# CC_pwr-moteur.net
KiCad netlist of a schematic drawn in Altium Designer
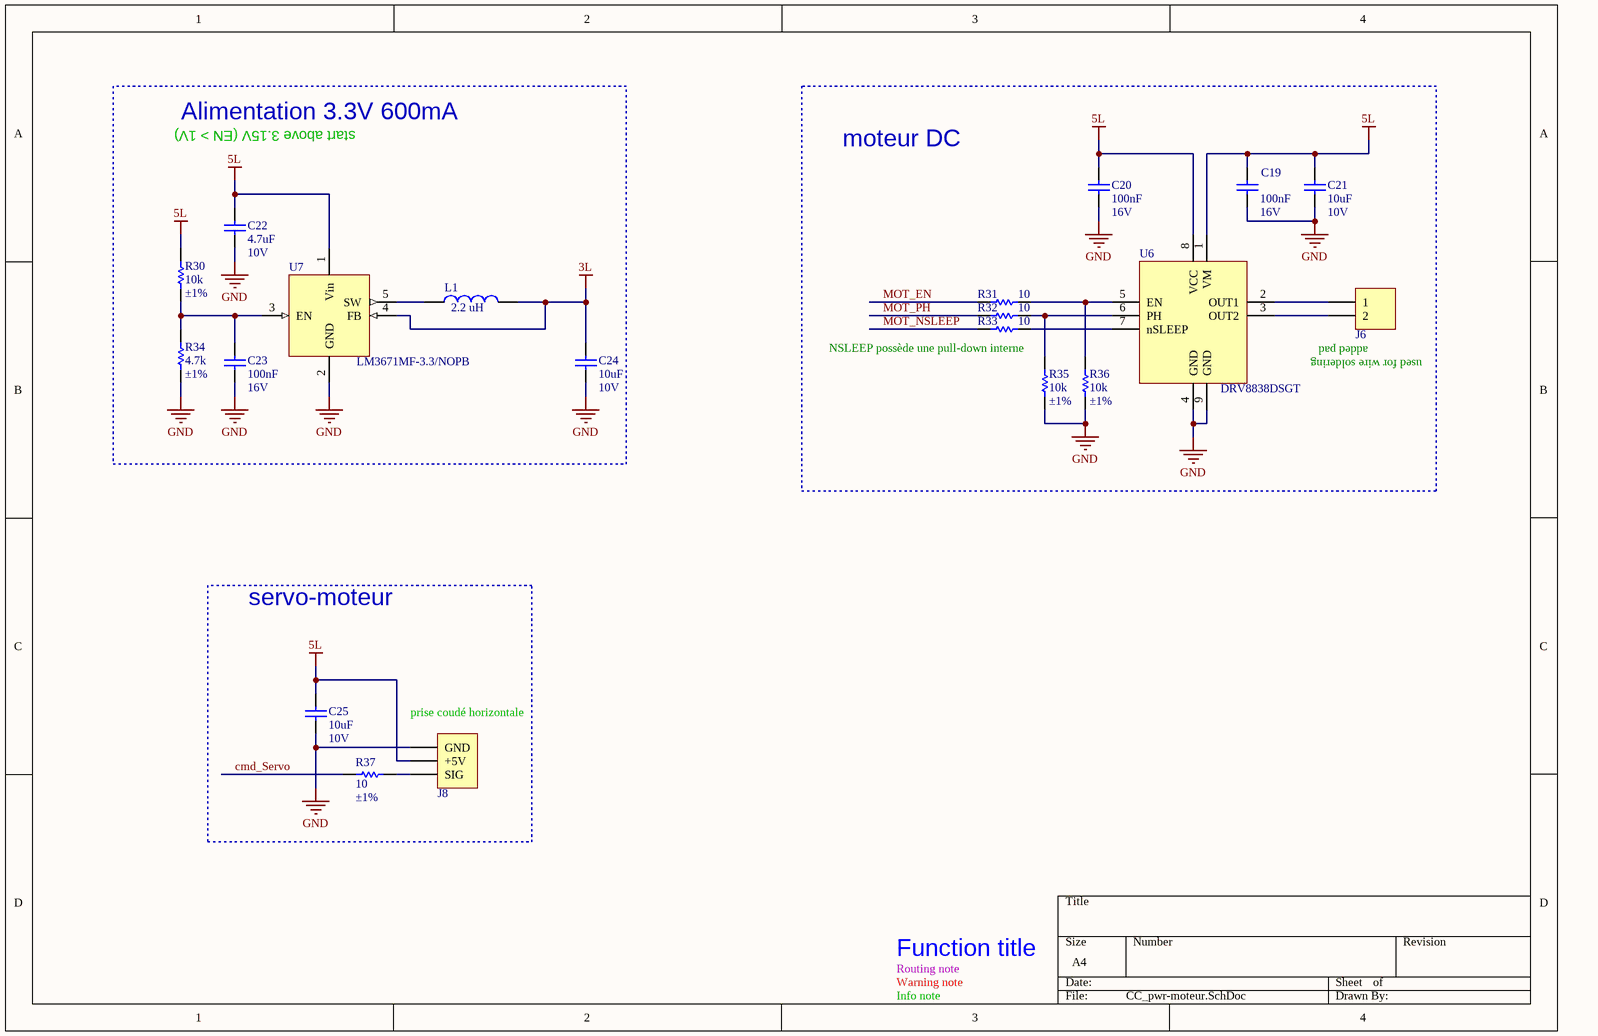
[diagram p0: CC_pwr-moteur.SchDoc]

(export (version "E")
  (design (tool "Eeschema 10.0.6"))
  (components
    (comp (ref "C19")
      (value "100nF")
      (footprint "WCAP-CSGP_0402, 1x0.5x0.5")
      (description "CAP CER 100nF 16V X7R 0402")
      (fields
        (field (name "MANUFACTURER") "Wurth Elektronik")
        (field (name "MANUFACTURER PART NUMBER") "885012205037")
        (field (name "RATEDVOLTAGE") "16V")
      )
      (libsource (lib "Condensateur") (part "WCAP-CSGP, 885012205037"))
    )
    (comp (ref "C20")
      (value "100nF")
      (footprint "WCAP-CSGP_0402, 1x0.5x0.5")
      (description "CAP CER 100nF 16V X7R 0402")
      (fields
        (field (name "MANUFACTURER") "Wurth Elektronik")
        (field (name "MANUFACTURER PART NUMBER") "885012205037")
        (field (name "RATEDVOLTAGE") "16V")
      )
      (libsource (lib "Condensateur") (part "WCAP-CSGP, 885012205037"))
    )
    (comp (ref "C21")
      (value "10uF")
      (footprint "WCAP-CSGP_0805, 2x1.25x1.25")
      (description "CAP CER 10uF 10V X7R 0805")
      (fields
        (field (name "MANUFACTURER") "Wurth Elektronik")
        (field (name "MANUFACTURER PART NUMBER") "885012207026")
        (field (name "RATEDVOLTAGE") "10V")
      )
      (libsource (lib "Condensateur") (part "WCAP-CSGP, 885012207026"))
    )
    (comp (ref "C22")
      (value "4.7uF")
      (footprint "WCAP-CSGP_0603, 1.6x0.8x0.8")
      (description "CAP CER 4.7UF 10V X5R 0603")
      (fields
        (field (name "MANUFACTURER") "Wurth Elektronik")
        (field (name "MANUFACTURER PART NUMBER") "885012106012")
        (field (name "RATEDVOLTAGE") "10V")
      )
      (libsource (lib "Condensateur") (part "WCAP-CSGP, 885012106012"))
    )
    (comp (ref "C23")
      (value "100nF")
      (footprint "WCAP-CSGP_0402, 1x0.5x0.5")
      (description "CAP CER 100nF 16V X7R 0402")
      (fields
        (field (name "MANUFACTURER") "Wurth Elektronik")
        (field (name "MANUFACTURER PART NUMBER") "885012205037")
        (field (name "RATEDVOLTAGE") "16V")
      )
      (libsource (lib "Condensateur") (part "WCAP-CSGP, 885012205037"))
    )
    (comp (ref "C24")
      (value "10uF")
      (footprint "WCAP-CSGP_0805, 2x1.25x1.25")
      (description "CAP CER 10uF 10V X7R 0805")
      (fields
        (field (name "MANUFACTURER") "Wurth Elektronik")
        (field (name "MANUFACTURER PART NUMBER") "885012207026")
        (field (name "RATEDVOLTAGE") "10V")
      )
      (libsource (lib "Condensateur") (part "WCAP-CSGP, 885012207026"))
    )
    (comp (ref "C25")
      (value "10uF")
      (footprint "WCAP-CSGP_0805, 2x1.25x1.25")
      (description "CAP CER 10uF 10V X7R 0805")
      (fields
        (field (name "MANUFACTURER") "Wurth Elektronik")
        (field (name "MANUFACTURER PART NUMBER") "885012207026")
        (field (name "RATEDVOLTAGE") "10V")
      )
      (libsource (lib "Condensateur") (part "WCAP-CSGP, 885012207026"))
    )
    (comp (ref "J6")
      (value "653102131822")
      (footprint "653102131822")
      (description "WR-WTB 2 horiz. 1.25mm")
      (fields (field (name "MANUFACTURER") "Wurth Electronics Inc."))
      (libsource (lib "Connecteurs") (part "653102131822"))
    )
    (comp (ref "J8")
      (value "61300311021")
      (footprint "61300311021")
      (description "CONN HEADER 3p horiz. 2.54mm")
      (fields (field (name "MANUFACTURER") "Wurth Electronics Inc."))
      (libsource (lib "Connecteurs") (part "61300311021"))
    )
    (comp (ref "L1")
      (value "2.2 uH")
      (footprint "WE-LQS_2010")
      (description "FIXED IND 2.2UH 960MA 220 MOHM")
      (fields
        (field (name "MANUFACTURER") "Wurth Elektronik")
        (field (name "MANUFACTURER PART NUMBER") "74404020022")
      )
      (libsource (lib "Inductance") (part "74404020022"))
    )
    (comp (ref "R30")
      (value "10k")
      (footprint "RESC1005X04N")
      (description "RES SMD 10K OHM 1% 1/16W 0402")
      (fields
        (field (name "POWER") "63mW")
        (field (name "MANUFACTURER") "Yageo")
        (field (name "PRECISION") "±1%")
      )
      (libsource (lib "Resistance") (part "RC0402FR-0710KL"))
    )
    (comp (ref "R31")
      (value "10")
      (footprint "RESC1005X04N")
      (description "RES SMD 10 OHM 1% 1/16W 0402")
      (fields (field (name "POWER") "63mW") (field (name "MANUFACTURER") "Yageo"))
      (libsource (lib "Resistance") (part "RC0402FR-0710RL"))
    )
    (comp (ref "R32")
      (value "10")
      (footprint "RESC1005X04N")
      (description "RES SMD 10 OHM 1% 1/16W 0402")
      (fields (field (name "POWER") "63mW") (field (name "MANUFACTURER") "Yageo"))
      (libsource (lib "Resistance") (part "RC0402FR-0710RL"))
    )
    (comp (ref "R33")
      (value "10")
      (footprint "RESC1005X04N")
      (description "RES SMD 10 OHM 1% 1/16W 0402")
      (fields (field (name "POWER") "63mW") (field (name "MANUFACTURER") "Yageo"))
      (libsource (lib "Resistance") (part "RC0402FR-0710RL"))
    )
    (comp (ref "R34")
      (value "4.7k")
      (footprint "RESC1005X04N")
      (description "RES SMD 4K7 OHM 1% 1/16W 0402")
      (fields
        (field (name "POWER") "63mW")
        (field (name "MANUFACTURER") "Yageo")
        (field (name "PRECISION") "±1%")
      )
      (libsource (lib "Resistance") (part "RC0402FR-074K7L"))
    )
    (comp (ref "R35")
      (value "10k")
      (footprint "RESC1005X04N")
      (description "RES SMD 10K OHM 1% 1/16W 0402")
      (fields
        (field (name "POWER") "63mW")
        (field (name "MANUFACTURER") "Yageo")
        (field (name "PRECISION") "±1%")
      )
      (libsource (lib "Resistance") (part "RC0402FR-0710KL"))
    )
    (comp (ref "R36")
      (value "10k")
      (footprint "RESC1005X04N")
      (description "RES SMD 10K OHM 1% 1/16W 0402")
      (fields
        (field (name "POWER") "63mW")
        (field (name "MANUFACTURER") "Yageo")
        (field (name "PRECISION") "±1%")
      )
      (libsource (lib "Resistance") (part "RC0402FR-0710KL"))
    )
    (comp (ref "R37")
      (value "10")
      (footprint "RESC1005X04N")
      (description "RES SMD 10 OHM 1% 1/16W 0402")
      (fields
        (field (name "POWER") "63mW")
        (field (name "MANUFACTURER") "Yageo")
        (field (name "PRECISION") "±1%")
      )
      (libsource (lib "Resistance") (part "RC0402FR-0710RL"))
    )
    (comp (ref "U6")
      (value "DRV8838DSGT")
      (footprint "PSON50P200X80_HS-9N")
      (description "IC BRIDGE DRIVER PAR 8WSON")
      (fields (field (name "MANUFACTURER") "Texas Instruments"))
      (libsource (lib "CI") (part "DRV8838DSGT"))
    )
    (comp (ref "U7")
      (value "LM3671MF-3.3/NOPB")
      (footprint "SOT23-5")
      (description "IC REG BUCK 3.3V 0.6A SYNC SOT23")
      (fields (field (name "MANUFACTURER") "Texas Instruments"))
      (libsource (lib "Alimentation") (part "LM3671MF-3.3/NOPB"))
    )
  )
  (nets
    (net (code "1") (name "/MOT_EN") (class "Default")
      (node (ref "R31") (pin "1") (pinfunction "1_1") (pintype "passive"))
    )
    (net (code "2") (name "/MOT_NSLEEP") (class "Default")
      (node (ref "R33") (pin "1") (pinfunction "1_1") (pintype "passive"))
    )
    (net (code "3") (name "/MOT_PH") (class "Default")
      (node (ref "R32") (pin "1") (pinfunction "1_1") (pintype "passive"))
    )
    (net (code "4") (name "/cmd_Servo") (class "Default")
      (node (ref "R37") (pin "1") (pinfunction "1_1") (pintype "passive"))
    )
    (net (code "5") (name "3L") (class "Default")
      (node (ref "C24") (pin "2") (pinfunction "2_2") (pintype "passive"))
      (node (ref "L1") (pin "2") (pinfunction "2_2") (pintype "passive"))
      (node (ref "U7") (pin "4") (pinfunction "FB_4") (pintype "input"))
    )
    (net (code "6") (name "5L") (class "Default")
      (node (ref "C19") (pin "2") (pinfunction "2_2") (pintype "passive"))
      (node (ref "C20") (pin "2") (pinfunction "2_2") (pintype "passive"))
      (node (ref "C21") (pin "2") (pinfunction "2_2") (pintype "passive"))
      (node (ref "C22") (pin "2") (pinfunction "2_2") (pintype "passive"))
      (node (ref "C25") (pin "2") (pinfunction "2_2") (pintype "passive"))
      (node (ref "J8") (pin "2") (pinfunction "+5V_2") (pintype "passive"))
      (node (ref "R30") (pin "2") (pinfunction "2_2") (pintype "passive"))
      (node (ref "U6") (pin "1") (pinfunction "VM_1") (pintype "power_in"))
      (node (ref "U6") (pin "8") (pinfunction "VCC_8") (pintype "power_in"))
      (node (ref "U7") (pin "1") (pinfunction "Vin_1") (pintype "power_in"))
    )
    (net (code "7") (name "GND") (class "Default")
      (node (ref "C19") (pin "1") (pinfunction "1_1") (pintype "passive"))
      (node (ref "C20") (pin "1") (pinfunction "1_1") (pintype "passive"))
      (node (ref "C21") (pin "1") (pinfunction "1_1") (pintype "passive"))
      (node (ref "C22") (pin "1") (pinfunction "1_1") (pintype "passive"))
      (node (ref "C23") (pin "1") (pinfunction "1_1") (pintype "passive"))
      (node (ref "C24") (pin "1") (pinfunction "1_1") (pintype "passive"))
      (node (ref "C25") (pin "1") (pinfunction "1_1") (pintype "passive"))
      (node (ref "J8") (pin "1") (pinfunction "GND_1") (pintype "passive"))
      (node (ref "R34") (pin "1") (pinfunction "1_1") (pintype "passive"))
      (node (ref "R35") (pin "1") (pinfunction "1_1") (pintype "passive"))
      (node (ref "R36") (pin "1") (pinfunction "1_1") (pintype "passive"))
      (node (ref "U6") (pin "4") (pinfunction "GND_4") (pintype "power_in"))
      (node (ref "U6") (pin "9") (pinfunction "GND_9") (pintype "power_in"))
      (node (ref "U7") (pin "2") (pinfunction "GND_2") (pintype "power_in"))
    )
    (net (code "8") (name "Net-(J8-SIG)") (class "Default")
      (node (ref "J8") (pin "3") (pinfunction "SIG_3") (pintype "passive"))
      (node (ref "R37") (pin "2") (pinfunction "2_2") (pintype "passive"))
    )
    (net (code "9") (name "Net-(U6-EN)") (class "Default")
      (node (ref "R31") (pin "2") (pinfunction "2_2") (pintype "passive"))
      (node (ref "R36") (pin "2") (pinfunction "2_2") (pintype "passive"))
      (node (ref "U6") (pin "5") (pinfunction "EN_5") (pintype "passive"))
    )
    (net (code "10") (name "Net-(U6-OUT1)") (class "Default")
      (node (ref "J6") (pin "1") (pinfunction "1_1") (pintype "passive"))
      (node (ref "U6") (pin "2") (pinfunction "OUT1_2") (pintype "passive"))
    )
    (net (code "11") (name "Net-(U6-OUT2)") (class "Default")
      (node (ref "J6") (pin "2") (pinfunction "2_2") (pintype "passive"))
      (node (ref "U6") (pin "3") (pinfunction "OUT2_3") (pintype "passive"))
    )
    (net (code "12") (name "Net-(U6-PH)") (class "Default")
      (node (ref "R32") (pin "2") (pinfunction "2_2") (pintype "passive"))
      (node (ref "R35") (pin "2") (pinfunction "2_2") (pintype "passive"))
      (node (ref "U6") (pin "6") (pinfunction "PH_6") (pintype "passive"))
    )
    (net (code "13") (name "Net-(U6-nSLEEP)") (class "Default")
      (node (ref "R33") (pin "2") (pinfunction "2_2") (pintype "passive"))
      (node (ref "U6") (pin "7") (pinfunction "nSLEEP_7") (pintype "passive"))
    )
    (net (code "14") (name "Net-(U7-EN)") (class "Default")
      (node (ref "C23") (pin "2") (pinfunction "2_2") (pintype "passive"))
      (node (ref "R30") (pin "1") (pinfunction "1_1") (pintype "passive"))
      (node (ref "R34") (pin "2") (pinfunction "2_2") (pintype "passive"))
      (node (ref "U7") (pin "3") (pinfunction "EN_3") (pintype "input"))
    )
    (net (code "15") (name "Net-(U7-SW)") (class "Default")
      (node (ref "L1") (pin "1") (pinfunction "1_1") (pintype "passive"))
      (node (ref "U7") (pin "5") (pinfunction "SW_5") (pintype "output"))
    )
  )
)
